# MAX96717_COUPON_V2.net
KiCad netlist of a schematic drawn in Altium Designer
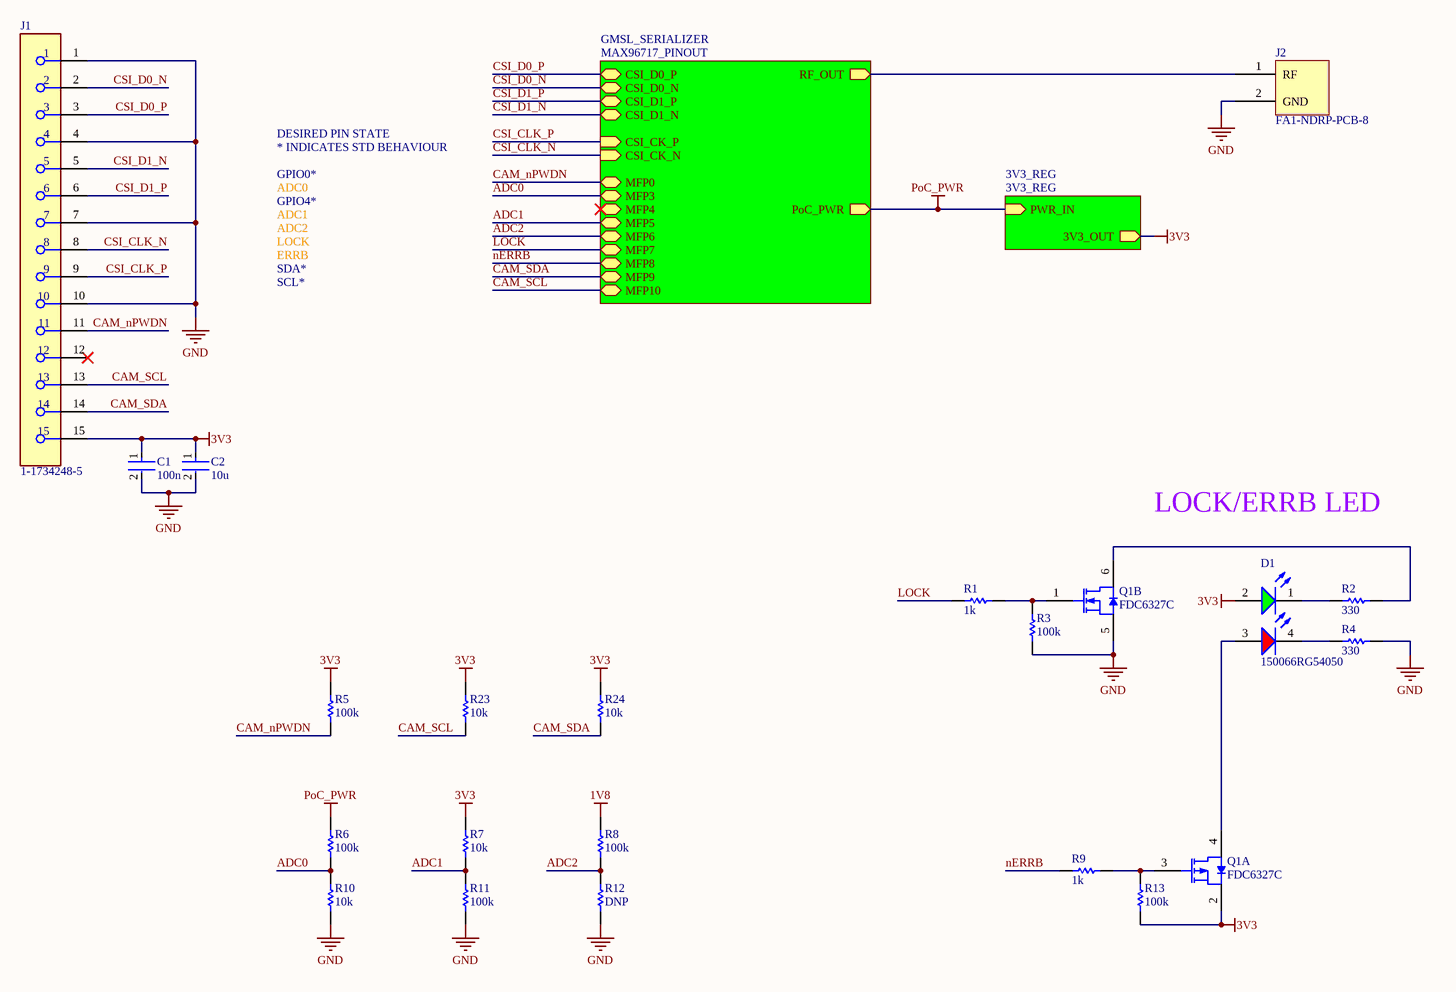
[diagram p0: MAX96717_COUPON_V2.SchDoc]

(export (version "E")
  (design (tool "Eeschema 10.0.6"))
  (components
    (comp (ref "C1")
      (value "100n")
      (footprint "FP-0402-L_1_0_0_05-W_0_5-IPC_A")
      (description "LARGE PADS, 0402 CAP, CHANGE COMMENT TO MATCH REAL P/N")
      (libsource (lib "Space Concordia") (part "b4654b650e69147ec39a6b967a45e02"))
    )
    (comp (ref "C2")
      (value "10u")
      (footprint "FP-0402-L_1_0_0_05-W_0_5-IPC_A")
      (description "LARGE PADS, 0402 CAP, CHANGE COMMENT TO MATCH REAL P/N")
      (libsource (lib "Space Concordia") (part "b4654b650e69147ec39a6b967a45e02"))
    )
    (comp (ref "D1")
      (value "150066RG54050")
      (footprint "WL-SBCD_0606")
      (description "Led, Red/Grn, 180Mcd/230Mcd, 624Nm/525Nm Rohs Compliant: Yes")
      (fields (field (name "SOURCE") "rgled.SchLib"))
      (libsource (lib "Space Concordia") (part "CMP-004-00034-2"))
    )
    (comp (ref "J1")
      (value "1-1734248-5")
      (footprint "FP-1-1734248-5-MFG")
      (description "CONN FPC VERT 15POS 1.00MM SMD")
      (fields
        (field (name "MANUFACTURER") "TE")
        (field (name "OCTOPART") "https://octopart.com/1-1734248-5-te+connectivity-40620898")
      )
      (libsource (lib "Altium Content Vault") (part "a0777be16b290adccad2a8f9338c195"))
    )
    (comp (ref "J2")
      (value "FA1-NDRP-PCB-8")
      (footprint "FA1-NDRP-PCB-8-Footprint-1")
      (description "RF F Connector, Male, Board Mount, Solder Terminal, Plug")
      (libsource (lib "Space Concordia") (part "FA1-NDRP-PCB-8"))
    )
    (comp (ref "Q1")
      (value "FDC6327C")
      (footprint "FAIR-SOT23-6_V")
      (fields (field (name "MANUFACTURER") "Fairchild"))
      (libsource (lib "Altium Content Vault") (part "PEMOS-SGD-NEMOS-GSD-6"))
    )
    (comp (ref "R1")
      (value "1k")
      (footprint "R0603B")
      (description "Resistor")
      (libsource (lib "Space Concordia") (part "Resistor"))
    )
    (comp (ref "R2")
      (value "330")
      (footprint "R0603B")
      (description "Resistor")
      (libsource (lib "Space Concordia") (part "Resistor"))
    )
    (comp (ref "R3")
      (value "100k")
      (footprint "R0603B")
      (description "Resistor")
      (libsource (lib "Space Concordia") (part "Resistor"))
    )
    (comp (ref "R4")
      (value "330")
      (footprint "R0603B")
      (description "Resistor")
      (libsource (lib "Space Concordia") (part "Resistor"))
    )
    (comp (ref "R5")
      (value "100k")
      (footprint "R0603B")
      (description "Resistor")
      (libsource (lib "Space Concordia") (part "Resistor"))
    )
    (comp (ref "R6")
      (value "100k")
      (footprint "R0603B")
      (description "Resistor")
      (libsource (lib "Space Concordia") (part "Resistor"))
    )
    (comp (ref "R7")
      (value "10k")
      (footprint "R0603B")
      (description "Resistor")
      (libsource (lib "Space Concordia") (part "Resistor"))
    )
    (comp (ref "R8")
      (value "100k")
      (footprint "R0603B")
      (description "Resistor")
      (libsource (lib "Space Concordia") (part "Resistor"))
    )
    (comp (ref "R9")
      (value "1k")
      (footprint "R0603B")
      (description "Resistor")
      (libsource (lib "Space Concordia") (part "Resistor"))
    )
    (comp (ref "R10")
      (value "10k")
      (footprint "R0603B")
      (description "Resistor")
      (libsource (lib "Space Concordia") (part "Resistor"))
    )
    (comp (ref "R11")
      (value "100k")
      (footprint "R0603B")
      (description "Resistor")
      (libsource (lib "Space Concordia") (part "Resistor"))
    )
    (comp (ref "R12")
      (value "DNP")
      (footprint "R0603B")
      (description "Resistor")
      (libsource (lib "Space Concordia") (part "Resistor"))
    )
    (comp (ref "R13")
      (value "100k")
      (footprint "R0603B")
      (description "Resistor")
      (libsource (lib "Space Concordia") (part "Resistor"))
    )
    (comp (ref "R23")
      (value "10k")
      (footprint "R0603B")
      (description "Resistor")
      (libsource (lib "Space Concordia") (part "Resistor"))
    )
    (comp (ref "R24")
      (value "10k")
      (footprint "R0603B")
      (description "Resistor")
      (libsource (lib "Space Concordia") (part "Resistor"))
    )
  )
  (nets
    (net (code "1") (name "/ADC0") (class "Default")
      (node (ref "R10") (pin "2") (pinfunction "2_2") (pintype "passive"))
      (node (ref "R6") (pin "1") (pinfunction "1_1") (pintype "passive"))
    )
    (net (code "2") (name "/ADC1") (class "Default")
      (node (ref "R11") (pin "2") (pinfunction "2_2") (pintype "passive"))
      (node (ref "R7") (pin "1") (pinfunction "1_1") (pintype "passive"))
    )
    (net (code "3") (name "/ADC2") (class "Default")
      (node (ref "R12") (pin "2") (pinfunction "2_2") (pintype "passive"))
      (node (ref "R8") (pin "1") (pinfunction "1_1") (pintype "passive"))
    )
    (net (code "4") (name "/CAM_SCL") (class "Default")
      (node (ref "J1") (pin "13") (pinfunction "13_13") (pintype "passive"))
      (node (ref "R23") (pin "1") (pinfunction "1_1") (pintype "passive"))
    )
    (net (code "5") (name "/CAM_SDA") (class "Default")
      (node (ref "J1") (pin "14") (pinfunction "14_14") (pintype "passive"))
      (node (ref "R24") (pin "1") (pinfunction "1_1") (pintype "passive"))
    )
    (net (code "6") (name "/CAM_nPWDN") (class "Default")
      (node (ref "J1") (pin "11") (pinfunction "11_11") (pintype "passive"))
      (node (ref "R5") (pin "1") (pinfunction "1_1") (pintype "passive"))
    )
    (net (code "7") (name "/CSI_CLK_N") (class "Default")
      (node (ref "J1") (pin "8") (pinfunction "8_8") (pintype "passive"))
    )
    (net (code "8") (name "/CSI_CLK_P") (class "Default")
      (node (ref "J1") (pin "9") (pinfunction "9_9") (pintype "passive"))
    )
    (net (code "9") (name "/CSI_D0_N") (class "Default")
      (node (ref "J1") (pin "2") (pinfunction "2_2") (pintype "passive"))
    )
    (net (code "10") (name "/CSI_D0_P") (class "Default")
      (node (ref "J1") (pin "3") (pinfunction "3_3") (pintype "passive"))
    )
    (net (code "11") (name "/CSI_D1_N") (class "Default")
      (node (ref "J1") (pin "5") (pinfunction "5_5") (pintype "passive"))
    )
    (net (code "12") (name "/CSI_D1_P") (class "Default")
      (node (ref "J1") (pin "6") (pinfunction "6_6") (pintype "passive"))
    )
    (net (code "13") (name "/LOCK") (class "Default")
      (node (ref "R1") (pin "2") (pinfunction "2_2") (pintype "passive"))
    )
    (net (code "15") (name "/RF_OUT") (class "Default")
      (node (ref "J2") (pin "1") (pinfunction "RF_1") (pintype "passive"))
    )
    (net (code "16") (name "/nERRB") (class "Default")
      (node (ref "R9") (pin "1") (pinfunction "1_1") (pintype "passive"))
    )
    (net (code "17") (name "1V8") (class "Default")
      (node (ref "R8") (pin "2") (pinfunction "2_2") (pintype "passive"))
    )
    (net (code "18") (name "3V3") (class "Default")
      (node (ref "C1") (pin "1") (pinfunction "1_1") (pintype "passive"))
      (node (ref "C2") (pin "1") (pinfunction "1_1") (pintype "passive"))
      (node (ref "D1") (pin "2") (pinfunction "A_2") (pintype "passive"))
      (node (ref "J1") (pin "15") (pinfunction "15_15") (pintype "passive"))
      (node (ref "Q1") (pin "2") (pinfunction "S_2") (pintype "passive"))
      (node (ref "R13") (pin "1") (pinfunction "1_1") (pintype "passive"))
      (node (ref "R23") (pin "2") (pinfunction "2_2") (pintype "passive"))
      (node (ref "R24") (pin "2") (pinfunction "2_2") (pintype "passive"))
      (node (ref "R5") (pin "2") (pinfunction "2_2") (pintype "passive"))
      (node (ref "R7") (pin "2") (pinfunction "2_2") (pintype "passive"))
    )
    (net (code "19") (name "GND") (class "Default")
      (node (ref "C1") (pin "2") (pinfunction "2_2") (pintype "passive"))
      (node (ref "C2") (pin "2") (pinfunction "2_2") (pintype "passive"))
      (node (ref "J1") (pin "1") (pinfunction "1_1") (pintype "passive"))
      (node (ref "J1") (pin "10") (pinfunction "10_10") (pintype "passive"))
      (node (ref "J1") (pin "4") (pinfunction "4_4") (pintype "passive"))
      (node (ref "J1") (pin "7") (pinfunction "7_7") (pintype "passive"))
      (node (ref "J2") (pin "2") (pinfunction "GND_2") (pintype "passive"))
      (node (ref "Q1") (pin "5") (pinfunction "S_5") (pintype "passive"))
      (node (ref "R10") (pin "1") (pinfunction "1_1") (pintype "passive"))
      (node (ref "R11") (pin "1") (pinfunction "1_1") (pintype "passive"))
      (node (ref "R12") (pin "1") (pinfunction "1_1") (pintype "passive"))
      (node (ref "R3") (pin "2") (pinfunction "2_2") (pintype "passive"))
      (node (ref "R4") (pin "1") (pinfunction "1_1") (pintype "passive"))
    )
    (net (code "20") (name "Net-(D1-K-Pad1)") (class "Default")
      (node (ref "D1") (pin "1") (pinfunction "K_1") (pintype "passive"))
      (node (ref "R2") (pin "2") (pinfunction "2_2") (pintype "passive"))
    )
    (net (code "21") (name "Net-(D1-K-Pad4)") (class "Default")
      (node (ref "D1") (pin "4") (pinfunction "K_4") (pintype "passive"))
      (node (ref "R4") (pin "2") (pinfunction "2_2") (pintype "passive"))
    )
    (net (code "22") (name "Net-(Q1A-D)") (class "Default")
      (node (ref "D1") (pin "3") (pinfunction "A_3") (pintype "passive"))
      (node (ref "Q1") (pin "4") (pinfunction "D_4") (pintype "passive"))
    )
    (net (code "23") (name "Net-(Q1A-G)") (class "Default")
      (node (ref "Q1") (pin "3") (pinfunction "G_3") (pintype "passive"))
      (node (ref "R13") (pin "2") (pinfunction "2_2") (pintype "passive"))
      (node (ref "R9") (pin "2") (pinfunction "2_2") (pintype "passive"))
    )
    (net (code "24") (name "Net-(Q1B-D)") (class "Default")
      (node (ref "Q1") (pin "6") (pinfunction "D_6") (pintype "passive"))
      (node (ref "R2") (pin "1") (pinfunction "1_1") (pintype "passive"))
    )
    (net (code "25") (name "Net-(Q1B-G)") (class "Default")
      (node (ref "Q1") (pin "1") (pinfunction "G_1") (pintype "passive"))
      (node (ref "R1") (pin "1") (pinfunction "1_1") (pintype "passive"))
      (node (ref "R3") (pin "1") (pinfunction "1_1") (pintype "passive"))
    )
    (net (code "26") (name "PoC_PWR") (class "Default")
      (node (ref "R6") (pin "2") (pinfunction "2_2") (pintype "passive"))
    )
    (net (code "27") (name "unconnected-(J1-Pad12)") (class "Default")
      (node (ref "J1") (pin "12") (pinfunction "12_12") (pintype "passive+no_connect"))
    )
  )
)
